# PCB-MicroSmartV.net
KiCad netlist of a schematic drawn in EAGLE
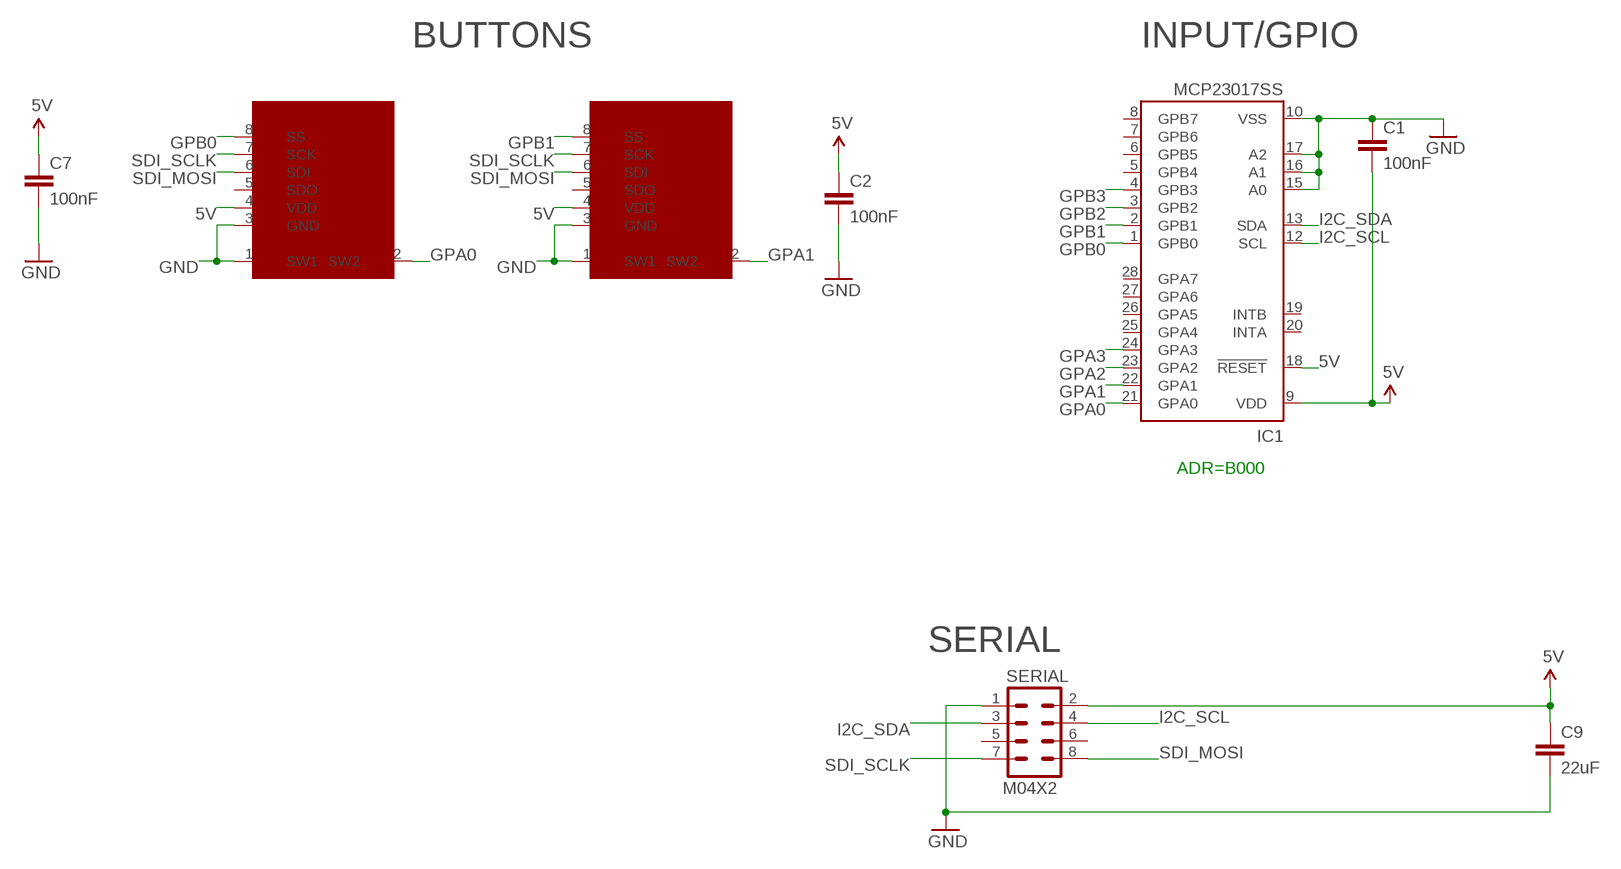
[diagram p0: schematic, sheet 1]

(export (version "E")
  (design (tool "Eeschema 10.0.6"))
  (components
    (comp (ref "C1")
      (value "100nF")
      (footprint "eagle-import:0603-CAP")
      (libsource (lib "eagle-import") (part "CAP0603-CAP"))
    )
    (comp (ref "C2")
      (value "100nF")
      (footprint "eagle-import:0603-CAP")
      (libsource (lib "eagle-import") (part "CAP0603-CAP"))
    )
    (comp (ref "C7")
      (value "100nF")
      (footprint "eagle-import:0603-CAP")
      (libsource (lib "eagle-import") (part "CAP0603-CAP"))
    )
    (comp (ref "C9")
      (value "22uF")
      (footprint "eagle-import:0805")
      (libsource (lib "eagle-import") (part "CAP0805"))
    )
    (comp (ref "IC1")
      (value "MCP23017SS")
      (footprint "eagle-import:SSOP28")
      (fields
        (field (name "MF") "MICROCHIP")
        (field (name "MPN") "MCP23017-E/SS")
        (field (name "MPN_1") "MCP23017-E/SS")
        (field (name "OC_FARNELL") "1467674")
        (field (name "OC_NEWARK") "31K2960")
      )
      (libsource (lib "eagle-import") (part "MCP23017SS"))
    )
    (comp (ref "SERIAL")
      (value "M04X2")
      (footprint "eagle-import:2X4")
      (libsource (lib "eagle-import") (part "M04X2"))
    )
    (comp (ref "SSW1")
      (value "SMART_SWITCHSMART_SWITCH_8PIN")
      (footprint "eagle-import:SMART_SWITCH")
      (libsource (lib "eagle-import") (part "SMART_SWITCHSMART_SWITCH_8PIN"))
    )
    (comp (ref "SSW2")
      (value "SMART_SWITCHSMART_SWITCH_8PIN")
      (footprint "eagle-import:SMART_SWITCH")
      (libsource (lib "eagle-import") (part "SMART_SWITCHSMART_SWITCH_8PIN"))
    )
  )
  (nets
    (net (code "1") (name "/GPA0") (class "Default")
      (node (ref "IC1") (pin "21") (pinfunction "GPA0_21") (pintype "bidirectional"))
      (node (ref "SSW1") (pin "2") (pinfunction "SW2_2") (pintype "bidirectional"))
    )
    (net (code "2") (name "/GPA1") (class "Default")
      (node (ref "IC1") (pin "22") (pinfunction "GPA1_22") (pintype "bidirectional"))
      (node (ref "SSW2") (pin "2") (pinfunction "SW2_2") (pintype "bidirectional"))
    )
    (net (code "3") (name "/GPA2") (class "Default")
      (node (ref "IC1") (pin "23") (pinfunction "GPA2_23") (pintype "bidirectional"))
    )
    (net (code "4") (name "/GPA3") (class "Default")
      (node (ref "IC1") (pin "24") (pinfunction "GPA3_24") (pintype "bidirectional"))
    )
    (net (code "5") (name "/GPB0") (class "Default")
      (node (ref "IC1") (pin "1") (pinfunction "GPB0_1") (pintype "bidirectional"))
      (node (ref "SSW1") (pin "8") (pinfunction "SS_8") (pintype "bidirectional"))
    )
    (net (code "6") (name "/GPB1") (class "Default")
      (node (ref "IC1") (pin "2") (pinfunction "GPB1_2") (pintype "bidirectional"))
      (node (ref "SSW2") (pin "8") (pinfunction "SS_8") (pintype "bidirectional"))
    )
    (net (code "7") (name "/GPB2") (class "Default")
      (node (ref "IC1") (pin "3") (pinfunction "GPB2_3") (pintype "bidirectional"))
    )
    (net (code "8") (name "/GPB3") (class "Default")
      (node (ref "IC1") (pin "4") (pinfunction "GPB3_4") (pintype "bidirectional"))
    )
    (net (code "9") (name "/I2C_SCL") (class "Default")
      (node (ref "IC1") (pin "12") (pinfunction "SCL_12") (pintype "input"))
      (node (ref "SERIAL") (pin "4") (pinfunction "4_4") (pintype "passive"))
    )
    (net (code "10") (name "/I2C_SDA") (class "Default")
      (node (ref "IC1") (pin "13") (pinfunction "SDA_13") (pintype "bidirectional"))
      (node (ref "SERIAL") (pin "3") (pinfunction "3_3") (pintype "passive"))
    )
    (net (code "11") (name "/SDI_MOSI") (class "Default")
      (node (ref "SERIAL") (pin "8") (pinfunction "8_8") (pintype "passive"))
      (node (ref "SSW1") (pin "6") (pinfunction "SDI_6") (pintype "bidirectional"))
      (node (ref "SSW2") (pin "6") (pinfunction "SDI_6") (pintype "bidirectional"))
    )
    (net (code "12") (name "/SDI_SCLK") (class "Default")
      (node (ref "SERIAL") (pin "7") (pinfunction "7_7") (pintype "passive"))
      (node (ref "SSW1") (pin "7") (pinfunction "SCK_7") (pintype "bidirectional"))
      (node (ref "SSW2") (pin "7") (pinfunction "SCK_7") (pintype "bidirectional"))
    )
    (net (code "13") (name "5V") (class "Default")
      (node (ref "C1") (pin "2") (pinfunction "2_2") (pintype "passive"))
      (node (ref "C2") (pin "1") (pinfunction "1_1") (pintype "passive"))
      (node (ref "C7") (pin "1") (pinfunction "1_1") (pintype "passive"))
      (node (ref "C9") (pin "1") (pinfunction "1_1") (pintype "passive"))
      (node (ref "IC1") (pin "18") (pinfunction "~{RESET}_18") (pintype "input"))
      (node (ref "IC1") (pin "9") (pinfunction "VDD_9") (pintype "power_in"))
      (node (ref "SERIAL") (pin "2") (pinfunction "2_2") (pintype "passive"))
      (node (ref "SSW1") (pin "4") (pinfunction "VDD_4") (pintype "bidirectional"))
      (node (ref "SSW2") (pin "4") (pinfunction "VDD_4") (pintype "bidirectional"))
    )
    (net (code "14") (name "GND") (class "Default")
      (node (ref "C1") (pin "1") (pinfunction "1_1") (pintype "passive"))
      (node (ref "C2") (pin "2") (pinfunction "2_2") (pintype "passive"))
      (node (ref "C7") (pin "2") (pinfunction "2_2") (pintype "passive"))
      (node (ref "C9") (pin "2") (pinfunction "2_2") (pintype "passive"))
      (node (ref "IC1") (pin "10") (pinfunction "VSS_10") (pintype "power_in"))
      (node (ref "IC1") (pin "15") (pinfunction "A0_15") (pintype "input"))
      (node (ref "IC1") (pin "16") (pinfunction "A1_16") (pintype "input"))
      (node (ref "IC1") (pin "17") (pinfunction "A2_17") (pintype "input"))
      (node (ref "SERIAL") (pin "1") (pinfunction "1_1") (pintype "passive"))
      (node (ref "SSW1") (pin "1") (pinfunction "SW1_1") (pintype "bidirectional"))
      (node (ref "SSW1") (pin "3") (pinfunction "GND_3") (pintype "bidirectional"))
      (node (ref "SSW2") (pin "1") (pinfunction "SW1_1") (pintype "bidirectional"))
      (node (ref "SSW2") (pin "3") (pinfunction "GND_3") (pintype "bidirectional"))
    )
    (net (code "15") (name "unconnected-(IC1-GPA4-Pad25)") (class "Default")
      (node (ref "IC1") (pin "25") (pinfunction "GPA4_25") (pintype "bidirectional"))
    )
    (net (code "16") (name "unconnected-(IC1-GPA5-Pad26)") (class "Default")
      (node (ref "IC1") (pin "26") (pinfunction "GPA5_26") (pintype "bidirectional"))
    )
    (net (code "17") (name "unconnected-(IC1-GPA6-Pad27)") (class "Default")
      (node (ref "IC1") (pin "27") (pinfunction "GPA6_27") (pintype "bidirectional"))
    )
    (net (code "18") (name "unconnected-(IC1-GPA7-Pad28)") (class "Default")
      (node (ref "IC1") (pin "28") (pinfunction "GPA7_28") (pintype "bidirectional"))
    )
    (net (code "19") (name "unconnected-(IC1-GPB4-Pad5)") (class "Default")
      (node (ref "IC1") (pin "5") (pinfunction "GPB4_5") (pintype "bidirectional"))
    )
    (net (code "20") (name "unconnected-(IC1-GPB5-Pad6)") (class "Default")
      (node (ref "IC1") (pin "6") (pinfunction "GPB5_6") (pintype "bidirectional"))
    )
    (net (code "21") (name "unconnected-(IC1-GPB6-Pad7)") (class "Default")
      (node (ref "IC1") (pin "7") (pinfunction "GPB6_7") (pintype "bidirectional"))
    )
    (net (code "22") (name "unconnected-(IC1-GPB7-Pad8)") (class "Default")
      (node (ref "IC1") (pin "8") (pinfunction "GPB7_8") (pintype "bidirectional"))
    )
    (net (code "23") (name "unconnected-(IC1-INTA-Pad20)") (class "Default")
      (node (ref "IC1") (pin "20") (pinfunction "INTA_20") (pintype "output"))
    )
    (net (code "24") (name "unconnected-(IC1-INTB-Pad19)") (class "Default")
      (node (ref "IC1") (pin "19") (pinfunction "INTB_19") (pintype "output"))
    )
    (net (code "25") (name "unconnected-(SERIAL-Pad5)") (class "Default")
      (node (ref "SERIAL") (pin "5") (pinfunction "5_5") (pintype "passive"))
    )
    (net (code "26") (name "unconnected-(SERIAL-Pad6)") (class "Default")
      (node (ref "SERIAL") (pin "6") (pinfunction "6_6") (pintype "passive"))
    )
    (net (code "27") (name "unconnected-(SSW1-SDO-Pad5)") (class "Default")
      (node (ref "SSW1") (pin "5") (pinfunction "SDO_5") (pintype "bidirectional"))
    )
    (net (code "28") (name "unconnected-(SSW2-SDO-Pad5)") (class "Default")
      (node (ref "SSW2") (pin "5") (pinfunction "SDO_5") (pintype "bidirectional"))
    )
  )
)
